# schematic.net
KiCad netlist of a schematic drawn in EAGLE
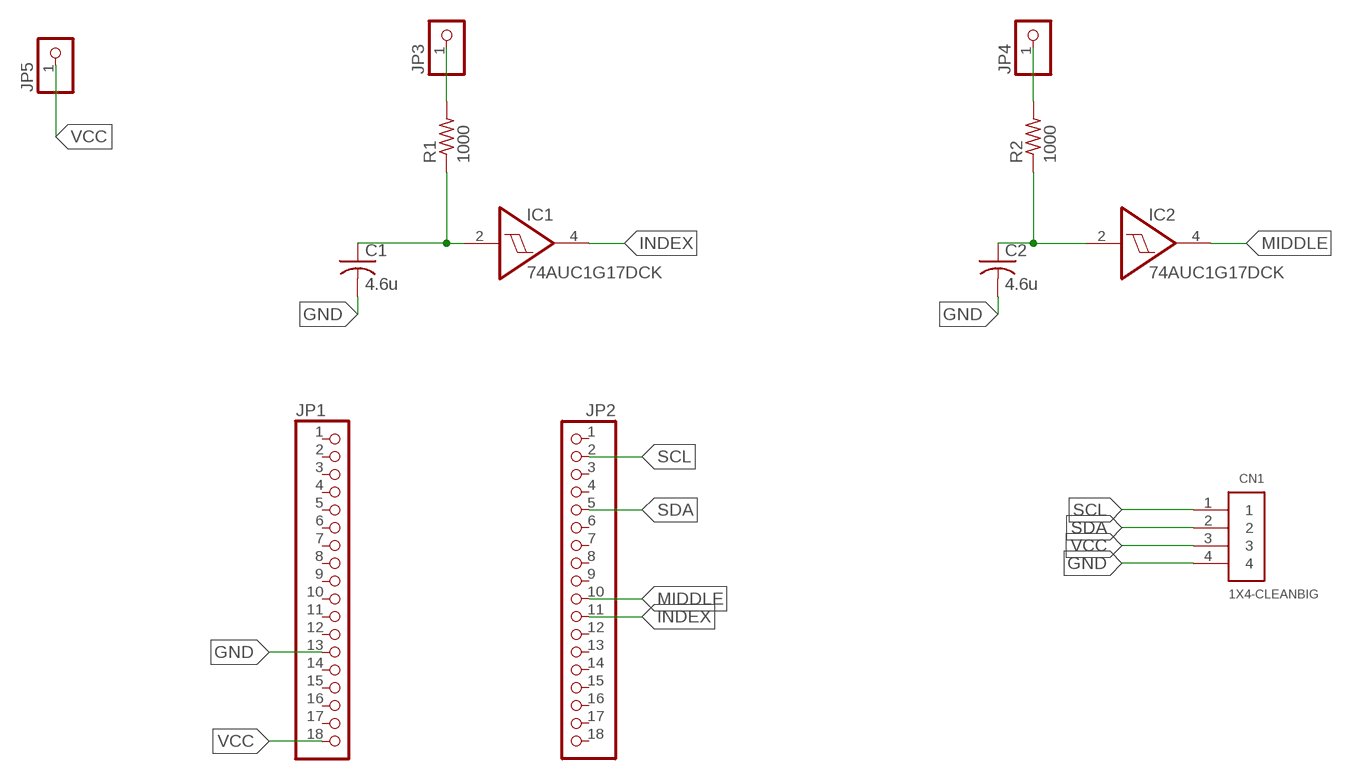
[diagram p0: schematic, sheet 1]

(export (version "E")
  (design (tool "Eeschema 10.0.6"))
  (components
    (comp (ref "C1")
      (value "4.6u")
      (footprint "eagle-import:C0805")
      (libsource (lib "eagle-import") (part "C-USC0805"))
    )
    (comp (ref "C2")
      (value "4.6u")
      (footprint "eagle-import:C0805")
      (libsource (lib "eagle-import") (part "C-USC0805"))
    )
    (comp (ref "CN1")
      (value "1X4-CLEANBIG")
      (footprint "eagle-import:1X04-CLEANBIG")
      (libsource (lib "eagle-import") (part "1X4-CLEANBIG"))
    )
    (comp (ref "IC1")
      (value "74AUC1G17DCK")
      (footprint "eagle-import:SC70-5")
      (libsource (lib "eagle-import") (part "741G17DCKAUC"))
    )
    (comp (ref "IC2")
      (value "74AUC1G17DCK")
      (footprint "eagle-import:SC70-5")
      (libsource (lib "eagle-import") (part "741G17DCKAUC"))
    )
    (comp (ref "JP1")
      (value "PINHD-1X18-BIG")
      (footprint "eagle-import:1X18-BIG")
      (libsource (lib "eagle-import") (part "PINHD-1X18-BIG"))
    )
    (comp (ref "JP2")
      (value "PINHD-1X18-BIG")
      (footprint "eagle-import:1X18-BIG")
      (libsource (lib "eagle-import") (part "PINHD-1X18-BIG"))
    )
    (comp (ref "JP3")
      (value "PINHD-1X1CB")
      (footprint "eagle-import:1X01-CLEANBIG")
      (libsource (lib "eagle-import") (part "PINHD-1X1CB"))
    )
    (comp (ref "JP4")
      (value "PINHD-1X1CB")
      (footprint "eagle-import:1X01-CLEANBIG")
      (libsource (lib "eagle-import") (part "PINHD-1X1CB"))
    )
    (comp (ref "JP5")
      (value "PINHD-1X1CB")
      (footprint "eagle-import:1X01-CLEANBIG")
      (libsource (lib "eagle-import") (part "PINHD-1X1CB"))
    )
    (comp (ref "R1")
      (value "1000")
      (footprint "eagle-import:M0805")
      (libsource (lib "eagle-import") (part "R-US_M0805"))
    )
    (comp (ref "R2")
      (value "1000")
      (footprint "eagle-import:M0805")
      (libsource (lib "eagle-import") (part "R-US_M0805"))
    )
  )
  (nets
    (net (code "1") (name "GND") (class "Default")
      (node (ref "C1") (pin "2") (pinfunction "2_2") (pintype "passive"))
      (node (ref "C2") (pin "2") (pinfunction "2_2") (pintype "passive"))
      (node (ref "CN1") (pin "4") (pinfunction "4_4") (pintype "bidirectional"))
      (node (ref "JP1") (pin "13") (pinfunction "13_13") (pintype "passive"))
    )
    (net (code "2") (name "INDEX") (class "Default")
      (node (ref "IC1") (pin "4") (pinfunction "O_4") (pintype "output"))
      (node (ref "JP2") (pin "11") (pinfunction "11_11") (pintype "passive"))
    )
    (net (code "3") (name "MIDDLE") (class "Default")
      (node (ref "IC2") (pin "4") (pinfunction "O_4") (pintype "output"))
      (node (ref "JP2") (pin "10") (pinfunction "10_10") (pintype "passive"))
    )
    (net (code "4") (name "Net-(IC1A-I)") (class "Default")
      (node (ref "C1") (pin "1") (pinfunction "1_1") (pintype "passive"))
      (node (ref "IC1") (pin "2") (pinfunction "I_2") (pintype "input"))
      (node (ref "R1") (pin "1") (pinfunction "1_1") (pintype "passive"))
    )
    (net (code "5") (name "Net-(IC2A-I)") (class "Default")
      (node (ref "C2") (pin "1") (pinfunction "1_1") (pintype "passive"))
      (node (ref "IC2") (pin "2") (pinfunction "I_2") (pintype "input"))
      (node (ref "R2") (pin "1") (pinfunction "1_1") (pintype "passive"))
    )
    (net (code "6") (name "Net-(JP3-Pad1)") (class "Default")
      (node (ref "JP3") (pin "1") (pinfunction "1_1") (pintype "passive"))
      (node (ref "R1") (pin "2") (pinfunction "2_2") (pintype "passive"))
    )
    (net (code "7") (name "Net-(JP4-Pad1)") (class "Default")
      (node (ref "JP4") (pin "1") (pinfunction "1_1") (pintype "passive"))
      (node (ref "R2") (pin "2") (pinfunction "2_2") (pintype "passive"))
    )
    (net (code "8") (name "SCL") (class "Default")
      (node (ref "CN1") (pin "1") (pinfunction "1_1") (pintype "bidirectional"))
      (node (ref "JP2") (pin "2") (pinfunction "2_2") (pintype "passive"))
    )
    (net (code "9") (name "SDA") (class "Default")
      (node (ref "CN1") (pin "2") (pinfunction "2_2") (pintype "bidirectional"))
      (node (ref "JP2") (pin "5") (pinfunction "5_5") (pintype "passive"))
    )
    (net (code "10") (name "VCC") (class "Default")
      (node (ref "CN1") (pin "3") (pinfunction "3_3") (pintype "bidirectional"))
      (node (ref "JP1") (pin "18") (pinfunction "18_18") (pintype "passive"))
      (node (ref "JP5") (pin "1") (pinfunction "1_1") (pintype "passive"))
    )
    (net (code "11") (name "unconnected-(JP1-Pad1)") (class "Default")
      (node (ref "JP1") (pin "1") (pinfunction "1_1") (pintype "passive"))
    )
    (net (code "12") (name "unconnected-(JP1-Pad2)") (class "Default")
      (node (ref "JP1") (pin "2") (pinfunction "2_2") (pintype "passive"))
    )
    (net (code "13") (name "unconnected-(JP1-Pad3)") (class "Default")
      (node (ref "JP1") (pin "3") (pinfunction "3_3") (pintype "passive"))
    )
    (net (code "14") (name "unconnected-(JP1-Pad4)") (class "Default")
      (node (ref "JP1") (pin "4") (pinfunction "4_4") (pintype "passive"))
    )
    (net (code "15") (name "unconnected-(JP1-Pad5)") (class "Default")
      (node (ref "JP1") (pin "5") (pinfunction "5_5") (pintype "passive"))
    )
    (net (code "16") (name "unconnected-(JP1-Pad6)") (class "Default")
      (node (ref "JP1") (pin "6") (pinfunction "6_6") (pintype "passive"))
    )
    (net (code "17") (name "unconnected-(JP1-Pad7)") (class "Default")
      (node (ref "JP1") (pin "7") (pinfunction "7_7") (pintype "passive"))
    )
    (net (code "18") (name "unconnected-(JP1-Pad8)") (class "Default")
      (node (ref "JP1") (pin "8") (pinfunction "8_8") (pintype "passive"))
    )
    (net (code "19") (name "unconnected-(JP1-Pad9)") (class "Default")
      (node (ref "JP1") (pin "9") (pinfunction "9_9") (pintype "passive"))
    )
    (net (code "20") (name "unconnected-(JP1-Pad10)") (class "Default")
      (node (ref "JP1") (pin "10") (pinfunction "10_10") (pintype "passive"))
    )
    (net (code "21") (name "unconnected-(JP1-Pad11)") (class "Default")
      (node (ref "JP1") (pin "11") (pinfunction "11_11") (pintype "passive"))
    )
    (net (code "22") (name "unconnected-(JP1-Pad12)") (class "Default")
      (node (ref "JP1") (pin "12") (pinfunction "12_12") (pintype "passive"))
    )
    (net (code "23") (name "unconnected-(JP1-Pad14)") (class "Default")
      (node (ref "JP1") (pin "14") (pinfunction "14_14") (pintype "passive"))
    )
    (net (code "24") (name "unconnected-(JP1-Pad15)") (class "Default")
      (node (ref "JP1") (pin "15") (pinfunction "15_15") (pintype "passive"))
    )
    (net (code "25") (name "unconnected-(JP1-Pad16)") (class "Default")
      (node (ref "JP1") (pin "16") (pinfunction "16_16") (pintype "passive"))
    )
    (net (code "26") (name "unconnected-(JP1-Pad17)") (class "Default")
      (node (ref "JP1") (pin "17") (pinfunction "17_17") (pintype "passive"))
    )
    (net (code "27") (name "unconnected-(JP2-Pad1)") (class "Default")
      (node (ref "JP2") (pin "1") (pinfunction "1_1") (pintype "passive"))
    )
    (net (code "28") (name "unconnected-(JP2-Pad3)") (class "Default")
      (node (ref "JP2") (pin "3") (pinfunction "3_3") (pintype "passive"))
    )
    (net (code "29") (name "unconnected-(JP2-Pad4)") (class "Default")
      (node (ref "JP2") (pin "4") (pinfunction "4_4") (pintype "passive"))
    )
    (net (code "30") (name "unconnected-(JP2-Pad6)") (class "Default")
      (node (ref "JP2") (pin "6") (pinfunction "6_6") (pintype "passive"))
    )
    (net (code "31") (name "unconnected-(JP2-Pad7)") (class "Default")
      (node (ref "JP2") (pin "7") (pinfunction "7_7") (pintype "passive"))
    )
    (net (code "32") (name "unconnected-(JP2-Pad8)") (class "Default")
      (node (ref "JP2") (pin "8") (pinfunction "8_8") (pintype "passive"))
    )
    (net (code "33") (name "unconnected-(JP2-Pad9)") (class "Default")
      (node (ref "JP2") (pin "9") (pinfunction "9_9") (pintype "passive"))
    )
    (net (code "34") (name "unconnected-(JP2-Pad12)") (class "Default")
      (node (ref "JP2") (pin "12") (pinfunction "12_12") (pintype "passive"))
    )
    (net (code "35") (name "unconnected-(JP2-Pad13)") (class "Default")
      (node (ref "JP2") (pin "13") (pinfunction "13_13") (pintype "passive"))
    )
    (net (code "36") (name "unconnected-(JP2-Pad14)") (class "Default")
      (node (ref "JP2") (pin "14") (pinfunction "14_14") (pintype "passive"))
    )
    (net (code "37") (name "unconnected-(JP2-Pad15)") (class "Default")
      (node (ref "JP2") (pin "15") (pinfunction "15_15") (pintype "passive"))
    )
    (net (code "38") (name "unconnected-(JP2-Pad16)") (class "Default")
      (node (ref "JP2") (pin "16") (pinfunction "16_16") (pintype "passive"))
    )
    (net (code "39") (name "unconnected-(JP2-Pad17)") (class "Default")
      (node (ref "JP2") (pin "17") (pinfunction "17_17") (pintype "passive"))
    )
    (net (code "40") (name "unconnected-(JP2-Pad18)") (class "Default")
      (node (ref "JP2") (pin "18") (pinfunction "18_18") (pintype "passive"))
    )
  )
)
